# 1-Schematic__777777.net
KiCad netlist of a schematic drawn in EasyEDA
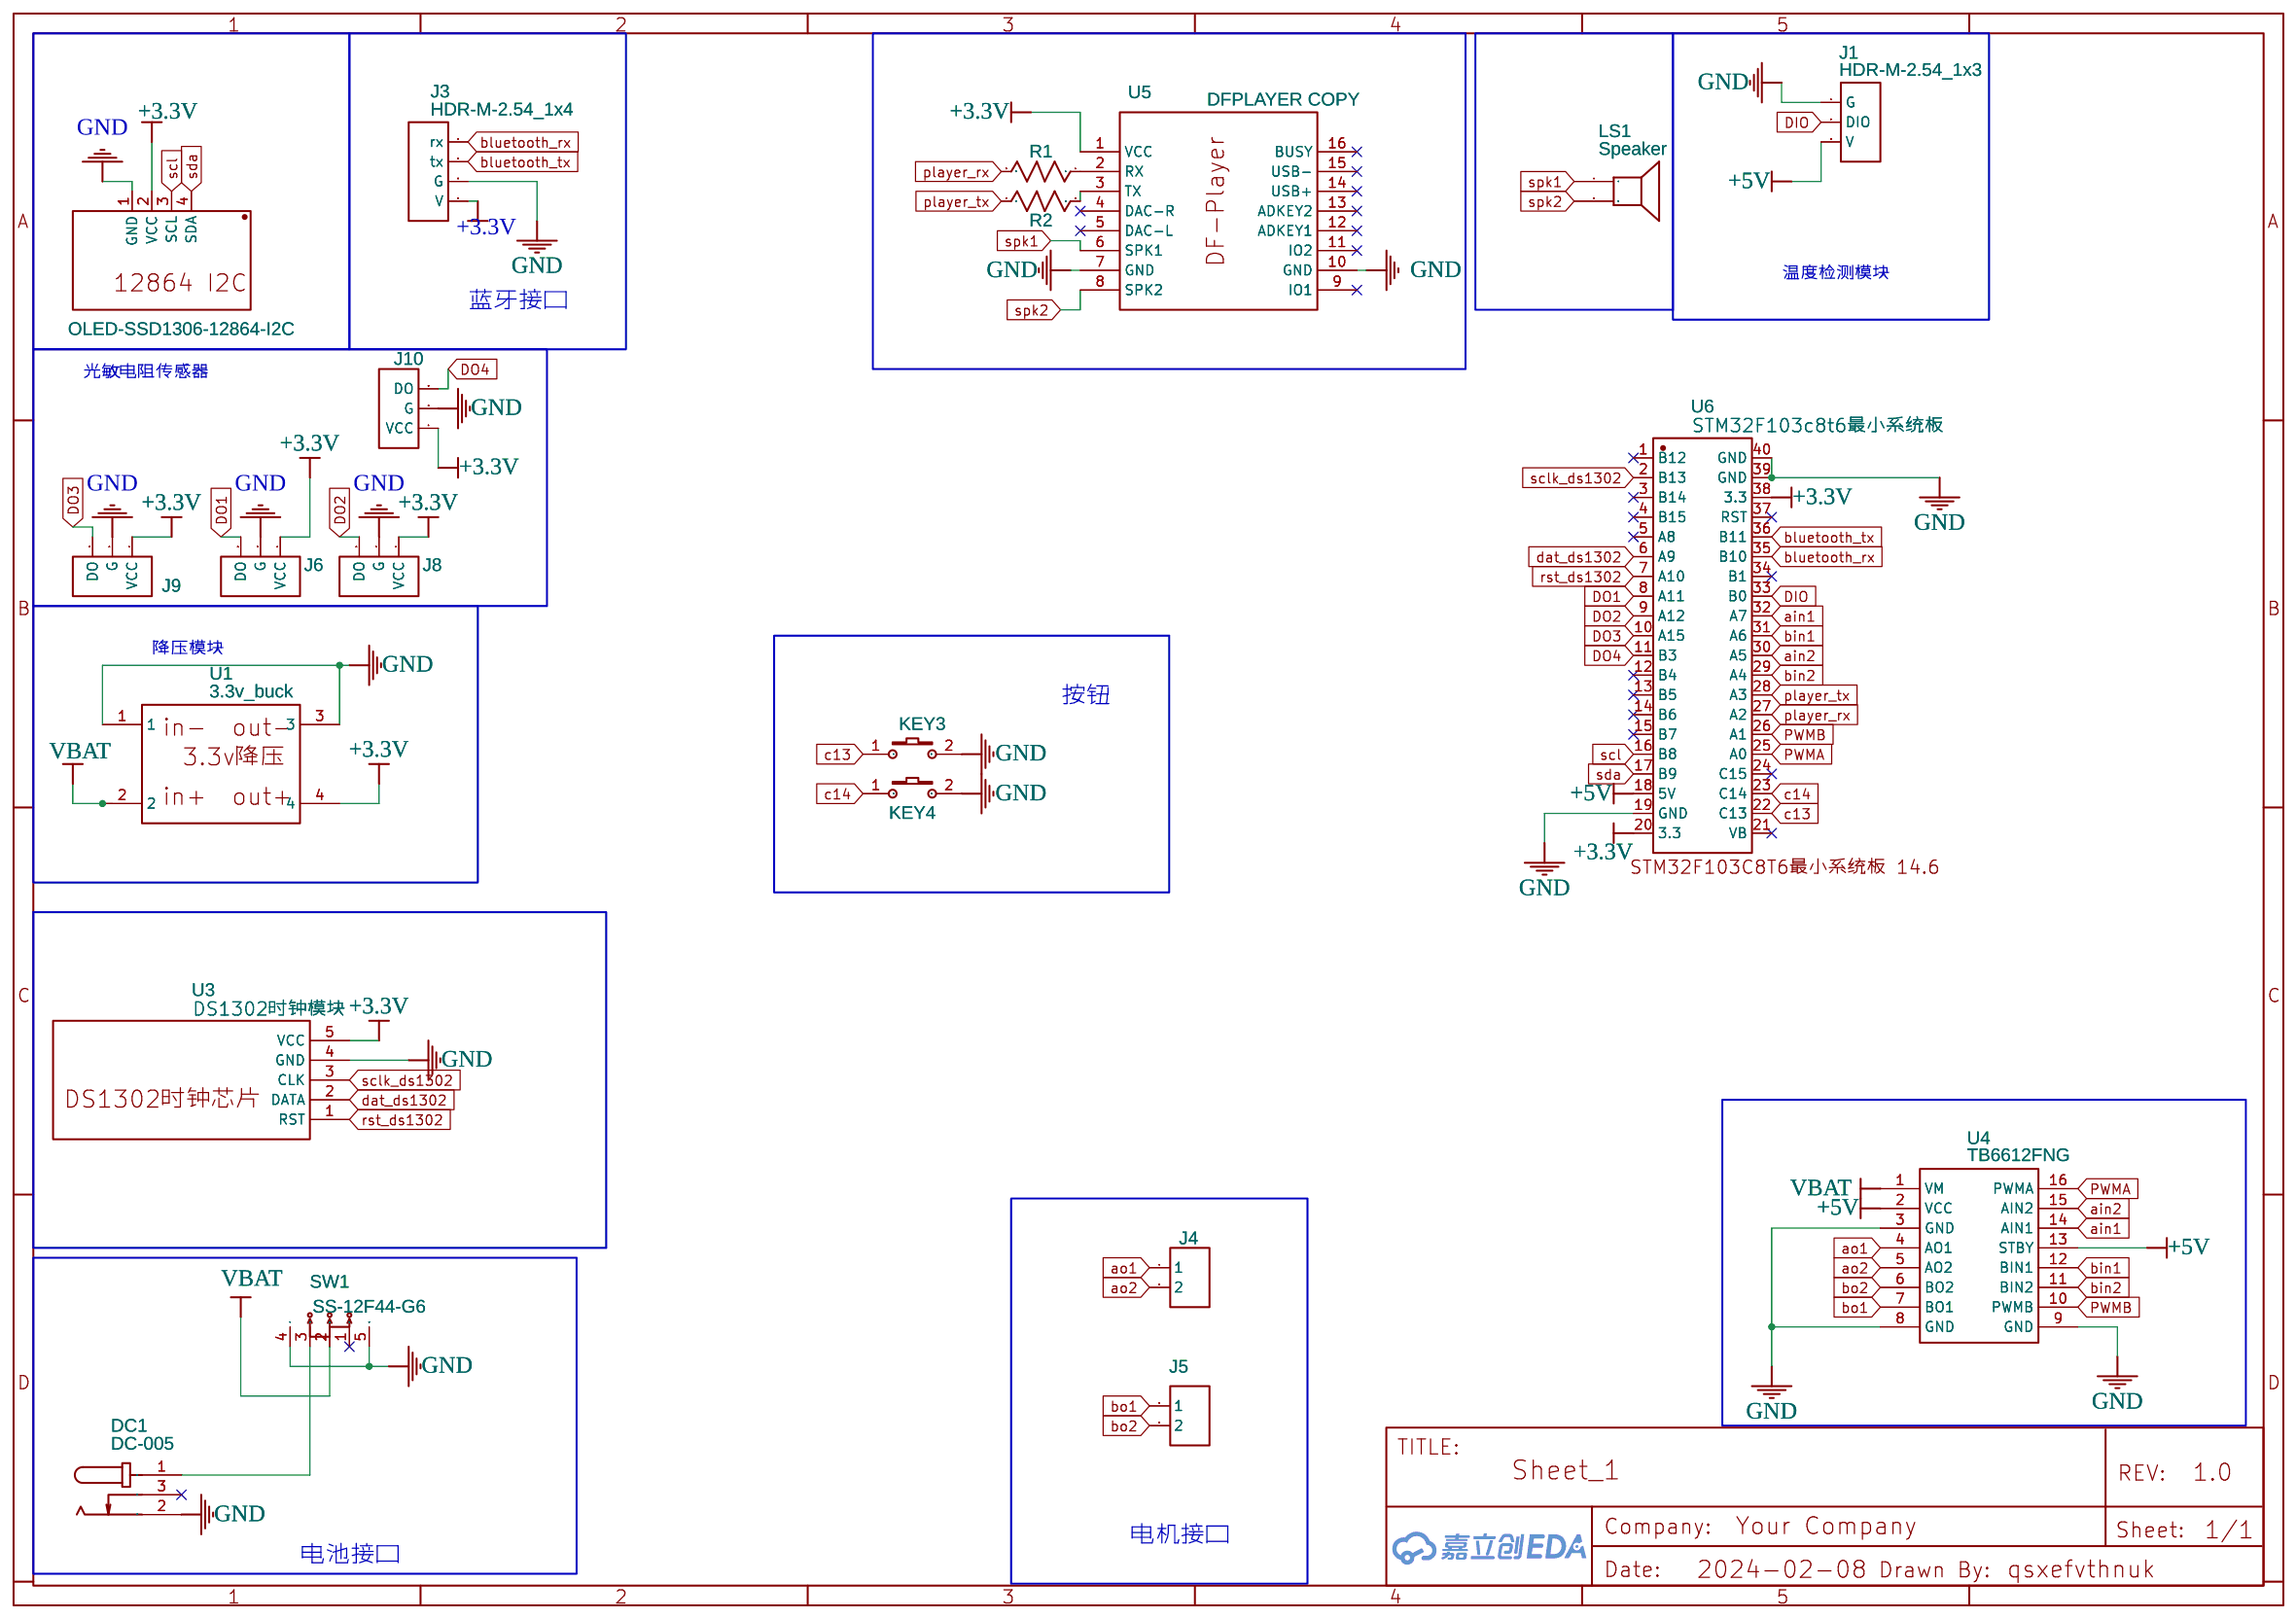
[diagram p0: schematic sheet]

(export (version "E")
  (design (tool "Eeschema 10.0.6"))
  (components
    (comp (ref "DC1") (value "DC-005") (libsource (lib "") (part "DC-005")))
    (comp (ref "J1") (value "HDR-M-2.54_1x3") (libsource (lib "") (part "HDR-M-2.54_1x3_1")))
    (comp (ref "J3") (value "HDR-M-2.54_1x4") (libsource (lib "") (part "HDR-M-2.54_1x4")))
    (comp (ref "J4") (value "HDR-M-2.54_1x2") (libsource (lib "") (part "HDR-M-2.54_1x2")))
    (comp (ref "J5") (value "HDR-M-2.54_1x2") (libsource (lib "") (part "HDR-M-2.54_1x2")))
    (comp (ref "J6") (value "语音播报") (libsource (lib "") (part "HDR-M-2.54_1x3")))
    (comp (ref "J8") (value "语音播报") (libsource (lib "") (part "HDR-M-2.54_1x3")))
    (comp (ref "J9") (value "语音播报") (libsource (lib "") (part "HDR-M-2.54_1x3")))
    (comp (ref "J10") (value "语音播报") (libsource (lib "") (part "HDR-M-2.54_1x3_2")))
    (comp (ref "KEY3")
      (value "K2-3.6×6.1_SMD")
      (fields (field (name "Manufacturer Part") "K2-1107ST-A4SW-06"))
      (libsource (lib "") (part "K2-3.6×6.1_SMD"))
    )
    (comp (ref "KEY4")
      (value "K2-3.6×6.1_SMD")
      (fields (field (name "Manufacturer Part") "K2-1107ST-A4SW-06"))
      (libsource (lib "") (part "K2-3.6×6.1_SMD"))
    )
    (comp (ref "LS1") (value "Speaker") (libsource (lib "") (part "Speaker")))
    (comp (ref "PCB1") (value "OLED-SSD1306-12864-I2C") (libsource (lib "") (part "OLED-SSD1306-12864-I2C")))
    (comp (ref "R1") (value "1k") (libsource (lib "") (part "R_0603_US_1")))
    (comp (ref "R2") (value "1k") (libsource (lib "") (part "R_0603_US")))
    (comp (ref "SW1")
      (value "SS-12F44-G6")
      (fields (field (name "Manufacturer") "USAKRO"))
      (libsource (lib "") (part "SS-12F44-G6"))
    )
    (comp (ref "U1") (value "3.3v_buck") (libsource (lib "") (part "5v_buck")))
    (comp (ref "U3") (value "DS1302时钟模块") (libsource (lib "") (part "DS1302时钟模块 COPY")))
    (comp (ref "U4") (value "TB6612FNG") (libsource (lib "") (part "TB6612FNG")))
    (comp (ref "U5")
      (value "DFPLAYER COPY")
      (fields (field (name "Manufacturer Part") "DFPLAYER"))
      (libsource (lib "") (part "DFPLAYER COPY"))
    )
    (comp (ref "U6") (value "STM32F103c8t6最小系统板") (libsource (lib "") (part "STM32F103c8t6最小系统板")))
  )
  (nets
    (net (code "1") (name "+3.3V") (class "Default")
      (node (ref "J10") (pin "1") (pinfunction "VCC_1") (pintype "unspecified"))
      (node (ref "J3") (pin "1") (pinfunction "V_1") (pintype "unspecified"))
      (node (ref "J6") (pin "1") (pinfunction "VCC_1") (pintype "unspecified"))
      (node (ref "J8") (pin "1") (pinfunction "VCC_1") (pintype "unspecified"))
      (node (ref "J9") (pin "1") (pinfunction "VCC_1") (pintype "unspecified"))
      (node (ref "PCB1") (pin "2") (pinfunction "VCC_2") (pintype "input"))
      (node (ref "U1") (pin "4") (pinfunction "4_4") (pintype "unspecified"))
      (node (ref "U3") (pin "5") (pinfunction "VCC_5") (pintype "unspecified"))
      (node (ref "U5") (pin "1") (pinfunction "VCC_1") (pintype "unspecified"))
      (node (ref "U6") (pin "20") (pinfunction "3.3_20") (pintype "unspecified"))
      (node (ref "U6") (pin "38") (pinfunction "3.3_38") (pintype "unspecified"))
    )
    (net (code "2") (name "+5V") (class "Default")
      (node (ref "J1") (pin "3") (pinfunction "V_3") (pintype "unspecified"))
      (node (ref "U4") (pin "13") (pinfunction "STBY_13") (pintype "unspecified"))
      (node (ref "U4") (pin "2") (pinfunction "VCC_2") (pintype "unspecified"))
      (node (ref "U6") (pin "18") (pinfunction "5V_18") (pintype "unspecified"))
    )
    (net (code "3") (name "DIO") (class "Default")
      (node (ref "J1") (pin "2") (pinfunction "DIO_2") (pintype "unspecified"))
      (node (ref "U6") (pin "33") (pinfunction "B0_33") (pintype "unspecified"))
    )
    (net (code "4") (name "DO1") (class "Default")
      (node (ref "J6") (pin "3") (pinfunction "DO_3") (pintype "unspecified"))
      (node (ref "U6") (pin "8") (pinfunction "A11_8") (pintype "unspecified"))
    )
    (net (code "5") (name "DO2") (class "Default")
      (node (ref "J8") (pin "3") (pinfunction "DO_3") (pintype "unspecified"))
      (node (ref "U6") (pin "9") (pinfunction "A12_9") (pintype "unspecified"))
    )
    (net (code "6") (name "DO3") (class "Default")
      (node (ref "J9") (pin "3") (pinfunction "DO_3") (pintype "unspecified"))
      (node (ref "U6") (pin "10") (pinfunction "A15_10") (pintype "unspecified"))
    )
    (net (code "7") (name "DO4") (class "Default")
      (node (ref "J10") (pin "3") (pinfunction "DO_3") (pintype "unspecified"))
      (node (ref "U6") (pin "11") (pinfunction "B3_11") (pintype "unspecified"))
    )
    (net (code "8") (name "GND") (class "Default")
      (node (ref "DC1") (pin "2") (pinfunction "2_2") (pintype "unspecified"))
      (node (ref "J1") (pin "1") (pinfunction "G_1") (pintype "unspecified"))
      (node (ref "J10") (pin "2") (pinfunction "G_2") (pintype "unspecified"))
      (node (ref "J3") (pin "2") (pinfunction "G_2") (pintype "unspecified"))
      (node (ref "J6") (pin "2") (pinfunction "G_2") (pintype "unspecified"))
      (node (ref "J8") (pin "2") (pinfunction "G_2") (pintype "unspecified"))
      (node (ref "J9") (pin "2") (pinfunction "G_2") (pintype "unspecified"))
      (node (ref "KEY3") (pin "2") (pinfunction "2_2") (pintype "unspecified"))
      (node (ref "KEY4") (pin "2") (pinfunction "2_2") (pintype "unspecified"))
      (node (ref "PCB1") (pin "1") (pinfunction "GND_1") (pintype "input"))
      (node (ref "SW1") (pin "4") (pinfunction "4_4") (pintype "unspecified"))
      (node (ref "SW1") (pin "5") (pinfunction "5_5") (pintype "unspecified"))
      (node (ref "U1") (pin "1") (pinfunction "1_1") (pintype "unspecified"))
      (node (ref "U1") (pin "3") (pinfunction "3_3") (pintype "unspecified"))
      (node (ref "U3") (pin "4") (pinfunction "GND_4") (pintype "unspecified"))
      (node (ref "U4") (pin "3") (pinfunction "GND_3") (pintype "unspecified"))
      (node (ref "U4") (pin "8") (pinfunction "GND_8") (pintype "passive"))
      (node (ref "U4") (pin "9") (pinfunction "GND_9") (pintype "unspecified"))
      (node (ref "U5") (pin "10") (pinfunction "GND_10") (pintype "unspecified"))
      (node (ref "U5") (pin "7") (pinfunction "GND_7") (pintype "unspecified"))
      (node (ref "U6") (pin "19") (pinfunction "GND_19") (pintype "unspecified"))
      (node (ref "U6") (pin "39") (pinfunction "GND_39") (pintype "unspecified"))
      (node (ref "U6") (pin "40") (pinfunction "GND_40") (pintype "unspecified"))
    )
    (net (code "9") (name "Net-(DC1-Pad1)") (class "Default")
      (node (ref "DC1") (pin "1") (pinfunction "1_1") (pintype "unspecified"))
      (node (ref "SW1") (pin "3") (pinfunction "3_3") (pintype "unspecified"))
    )
    (net (code "10") (name "Net-(U5-RX)") (class "Default")
      (node (ref "R1") (pin "1") (pinfunction "1_1") (pintype "unspecified"))
      (node (ref "U5") (pin "2") (pinfunction "RX_2") (pintype "unspecified"))
    )
    (net (code "11") (name "Net-(U5-TX)") (class "Default")
      (node (ref "R2") (pin "2") (pinfunction "2_2") (pintype "unspecified"))
      (node (ref "U5") (pin "3") (pinfunction "TX_3") (pintype "unspecified"))
    )
    (net (code "12") (name "PWMA") (class "Default")
      (node (ref "U4") (pin "16") (pinfunction "PWMA_16") (pintype "unspecified"))
      (node (ref "U6") (pin "25") (pinfunction "A0_25") (pintype "unspecified"))
    )
    (net (code "13") (name "PWMB") (class "Default")
      (node (ref "U4") (pin "10") (pinfunction "PWMB_10") (pintype "unspecified"))
      (node (ref "U6") (pin "26") (pinfunction "A1_26") (pintype "unspecified"))
    )
    (net (code "14") (name "VBAT") (class "Default")
      (node (ref "SW1") (pin "2") (pinfunction "2_2") (pintype "unspecified"))
      (node (ref "U1") (pin "2") (pinfunction "2_2") (pintype "unspecified"))
      (node (ref "U4") (pin "1") (pinfunction "VM_1") (pintype "unspecified"))
    )
    (net (code "15") (name "ain1") (class "Default")
      (node (ref "U4") (pin "14") (pinfunction "AIN1_14") (pintype "unspecified"))
      (node (ref "U6") (pin "32") (pinfunction "A7_32") (pintype "unspecified"))
    )
    (net (code "16") (name "ain2") (class "Default")
      (node (ref "U4") (pin "15") (pinfunction "AIN2_15") (pintype "unspecified"))
      (node (ref "U6") (pin "30") (pinfunction "A5_30") (pintype "unspecified"))
    )
    (net (code "17") (name "ao1") (class "Default")
      (node (ref "J4") (pin "1") (pinfunction "1_1") (pintype "unspecified"))
      (node (ref "U4") (pin "4") (pinfunction "AO1_4") (pintype "unspecified"))
    )
    (net (code "18") (name "ao2") (class "Default")
      (node (ref "J4") (pin "2") (pinfunction "2_2") (pintype "unspecified"))
      (node (ref "U4") (pin "5") (pinfunction "AO2_5") (pintype "unspecified"))
    )
    (net (code "19") (name "bin1") (class "Default")
      (node (ref "U4") (pin "12") (pinfunction "BIN1_12") (pintype "unspecified"))
      (node (ref "U6") (pin "31") (pinfunction "A6_31") (pintype "unspecified"))
    )
    (net (code "20") (name "bin2") (class "Default")
      (node (ref "U4") (pin "11") (pinfunction "BIN2_11") (pintype "unspecified"))
      (node (ref "U6") (pin "29") (pinfunction "A4_29") (pintype "unspecified"))
    )
    (net (code "21") (name "bluetooth_rx") (class "Default")
      (node (ref "J3") (pin "4") (pinfunction "rx_4") (pintype "unspecified"))
      (node (ref "U6") (pin "35") (pinfunction "B10_35") (pintype "unspecified"))
    )
    (net (code "22") (name "bluetooth_tx") (class "Default")
      (node (ref "J3") (pin "3") (pinfunction "tx_3") (pintype "unspecified"))
      (node (ref "U6") (pin "36") (pinfunction "B11_36") (pintype "unspecified"))
    )
    (net (code "23") (name "bo1") (class "Default")
      (node (ref "J5") (pin "1") (pinfunction "1_1") (pintype "unspecified"))
      (node (ref "U4") (pin "7") (pinfunction "BO1_7") (pintype "unspecified"))
    )
    (net (code "24") (name "bo2") (class "Default")
      (node (ref "J5") (pin "2") (pinfunction "2_2") (pintype "unspecified"))
      (node (ref "U4") (pin "6") (pinfunction "BO2_6") (pintype "unspecified"))
    )
    (net (code "25") (name "c13") (class "Default")
      (node (ref "KEY3") (pin "1") (pinfunction "1_1") (pintype "unspecified"))
      (node (ref "U6") (pin "22") (pinfunction "C13_22") (pintype "unspecified"))
    )
    (net (code "26") (name "c14") (class "Default")
      (node (ref "KEY4") (pin "1") (pinfunction "1_1") (pintype "unspecified"))
      (node (ref "U6") (pin "23") (pinfunction "C14_23") (pintype "unspecified"))
    )
    (net (code "27") (name "dat_ds1302") (class "Default")
      (node (ref "U3") (pin "2") (pinfunction "DATA_2") (pintype "unspecified"))
      (node (ref "U6") (pin "6") (pinfunction "A9_6") (pintype "unspecified"))
    )
    (net (code "28") (name "player_rx") (class "Default")
      (node (ref "R1") (pin "2") (pinfunction "2_2") (pintype "unspecified"))
      (node (ref "U6") (pin "27") (pinfunction "A2_27") (pintype "unspecified"))
    )
    (net (code "29") (name "player_tx") (class "Default")
      (node (ref "R2") (pin "1") (pinfunction "1_1") (pintype "unspecified"))
      (node (ref "U6") (pin "28") (pinfunction "A3_28") (pintype "unspecified"))
    )
    (net (code "30") (name "rst_ds1302") (class "Default")
      (node (ref "U3") (pin "1") (pinfunction "RST_1") (pintype "unspecified"))
      (node (ref "U6") (pin "7") (pinfunction "A10_7") (pintype "unspecified"))
    )
    (net (code "31") (name "scl") (class "Default")
      (node (ref "PCB1") (pin "3") (pinfunction "SCL_3") (pintype "passive"))
      (node (ref "U6") (pin "16") (pinfunction "B8_16") (pintype "unspecified"))
    )
    (net (code "32") (name "sclk_ds1302") (class "Default")
      (node (ref "U3") (pin "3") (pinfunction "CLK_3") (pintype "unspecified"))
      (node (ref "U6") (pin "2") (pinfunction "B13_2") (pintype "unspecified"))
    )
    (net (code "33") (name "sda") (class "Default")
      (node (ref "PCB1") (pin "4") (pinfunction "SDA_4") (pintype "passive"))
      (node (ref "U6") (pin "17") (pinfunction "B9_17") (pintype "unspecified"))
    )
    (net (code "34") (name "spk1") (class "Default")
      (node (ref "LS1") (pin "1") (pinfunction "1_1") (pintype "unspecified"))
      (node (ref "U5") (pin "6") (pinfunction "SPK1_6") (pintype "unspecified"))
    )
    (net (code "35") (name "spk2") (class "Default")
      (node (ref "LS1") (pin "2") (pinfunction "2_2") (pintype "unspecified"))
      (node (ref "U5") (pin "8") (pinfunction "SPK2_8") (pintype "unspecified"))
    )
    (net (code "36") (name "unconnected-(DC1-Pad3)") (class "Default")
      (node (ref "DC1") (pin "3") (pinfunction "3_3") (pintype "unspecified+no_connect"))
    )
    (net (code "37") (name "unconnected-(SW1-Pad1)") (class "Default")
      (node (ref "SW1") (pin "1") (pinfunction "1_1") (pintype "unspecified+no_connect"))
    )
    (net (code "38") (name "unconnected-(U5-ADKEY1-Pad12)") (class "Default")
      (node (ref "U5") (pin "12") (pinfunction "ADKEY1_12") (pintype "unspecified+no_connect"))
    )
    (net (code "39") (name "unconnected-(U5-ADKEY2-Pad13)") (class "Default")
      (node (ref "U5") (pin "13") (pinfunction "ADKEY2_13") (pintype "unspecified+no_connect"))
    )
    (net (code "40") (name "unconnected-(U5-BUSY-Pad16)") (class "Default")
      (node (ref "U5") (pin "16") (pinfunction "BUSY_16") (pintype "unspecified+no_connect"))
    )
    (net (code "41") (name "unconnected-(U5-DAC-L-Pad5)") (class "Default")
      (node (ref "U5") (pin "5") (pinfunction "DAC-L_5") (pintype "unspecified+no_connect"))
    )
    (net (code "42") (name "unconnected-(U5-DAC-R-Pad4)") (class "Default")
      (node (ref "U5") (pin "4") (pinfunction "DAC-R_4") (pintype "unspecified+no_connect"))
    )
    (net (code "43") (name "unconnected-(U5-IO1-Pad9)") (class "Default")
      (node (ref "U5") (pin "9") (pinfunction "IO1_9") (pintype "unspecified+no_connect"))
    )
    (net (code "44") (name "unconnected-(U5-IO2-Pad11)") (class "Default")
      (node (ref "U5") (pin "11") (pinfunction "IO2_11") (pintype "unspecified+no_connect"))
    )
    (net (code "45") (name "unconnected-(U5-USB+-Pad14)") (class "Default")
      (node (ref "U5") (pin "14") (pinfunction "USB+_14") (pintype "unspecified+no_connect"))
    )
    (net (code "46") (name "unconnected-(U5-USB--Pad15)") (class "Default")
      (node (ref "U5") (pin "15") (pinfunction "USB-_15") (pintype "unspecified+no_connect"))
    )
    (net (code "47") (name "unconnected-(U6-A8-Pad5)") (class "Default")
      (node (ref "U6") (pin "5") (pinfunction "A8_5") (pintype "unspecified+no_connect"))
    )
    (net (code "48") (name "unconnected-(U6-B1-Pad34)") (class "Default")
      (node (ref "U6") (pin "34") (pinfunction "B1_34") (pintype "unspecified+no_connect"))
    )
    (net (code "49") (name "unconnected-(U6-B4-Pad12)") (class "Default")
      (node (ref "U6") (pin "12") (pinfunction "B4_12") (pintype "unspecified+no_connect"))
    )
    (net (code "50") (name "unconnected-(U6-B5-Pad13)") (class "Default")
      (node (ref "U6") (pin "13") (pinfunction "B5_13") (pintype "unspecified+no_connect"))
    )
    (net (code "51") (name "unconnected-(U6-B6-Pad14)") (class "Default")
      (node (ref "U6") (pin "14") (pinfunction "B6_14") (pintype "unspecified+no_connect"))
    )
    (net (code "52") (name "unconnected-(U6-B7-Pad15)") (class "Default")
      (node (ref "U6") (pin "15") (pinfunction "B7_15") (pintype "unspecified+no_connect"))
    )
    (net (code "53") (name "unconnected-(U6-B12-Pad1)") (class "Default")
      (node (ref "U6") (pin "1") (pinfunction "B12_1") (pintype "unspecified+no_connect"))
    )
    (net (code "54") (name "unconnected-(U6-B14-Pad3)") (class "Default")
      (node (ref "U6") (pin "3") (pinfunction "B14_3") (pintype "unspecified+no_connect"))
    )
    (net (code "55") (name "unconnected-(U6-B15-Pad4)") (class "Default")
      (node (ref "U6") (pin "4") (pinfunction "B15_4") (pintype "unspecified+no_connect"))
    )
    (net (code "56") (name "unconnected-(U6-C15-Pad24)") (class "Default")
      (node (ref "U6") (pin "24") (pinfunction "C15_24") (pintype "unspecified+no_connect"))
    )
    (net (code "57") (name "unconnected-(U6-RST-Pad37)") (class "Default")
      (node (ref "U6") (pin "37") (pinfunction "RST_37") (pintype "unspecified+no_connect"))
    )
    (net (code "58") (name "unconnected-(U6-VB-Pad21)") (class "Default")
      (node (ref "U6") (pin "21") (pinfunction "VB_21") (pintype "unspecified+no_connect"))
    )
  )
)
